# Inverted_HS_LS_switch_HI_PWR.net
KiCad netlist of a schematic drawn in Altium Designer
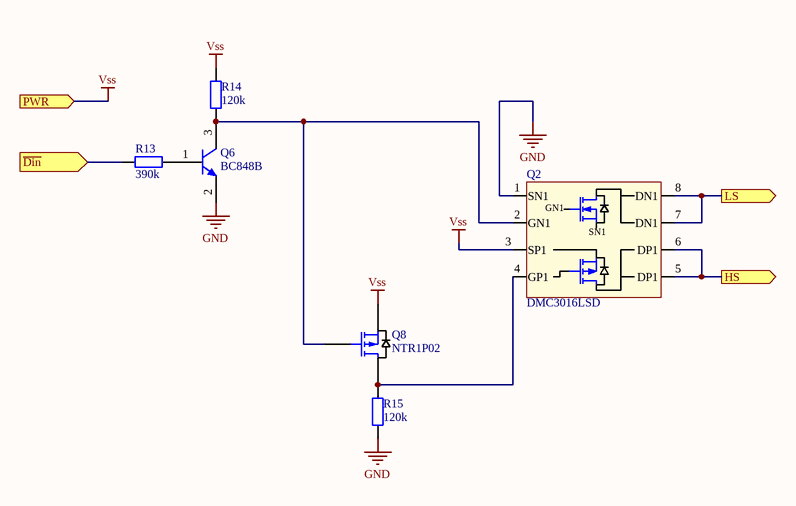
[diagram p0: Inverted_HS_LS_switch_HI_PWR.SchDoc]

(export (version "E")
  (design (tool "Eeschema 10.0.6"))
  (components
    (comp (ref "Q2")
      (value "DMC3016LSD")
      (footprint "SOIC-8_SOIC127P600X175-8N")
      (description "MOSFET N/P-CH 30V 8.2A/6.2A 8SO")
      (fields
        (field (name "MANUFACTURER") "Diodes")
        (field (name "MANUFACTURER PART NUMBER") "DMC3016LSD-13")
      )
      (libsource (lib "Datalogger") (part "DMC3016LSD"))
    )
    (comp (ref "Q6")
      (value "BC848B")
      (footprint "SOT23_N")
      (description "NPN Silicon AF Transistor, 30 V VCEO, 100 mA IC, SOT23, Reel, Green")
      (fields (field (name "MANUFACTURER") "Infineon"))
      (libsource (lib "Datalogger") (part "BC848B"))
    )
    (comp (ref "Q8")
      (value "NTR1P02")
      (footprint "SOT23_N")
      (description "NTR1P02T1G P-channel MOSFET Transistor; 1 A; 20 V; 3-Pin SOT-23")
      (fields (field (name "MANUFACTURER") "ON Semiconductor"))
      (libsource (lib "Datalogger") (part "MOSFET-P"))
    )
    (comp (ref "R13")
      (value "390k")
      (footprint "RES-1206_M")
      (description "Resistor")
      (fields (field (name "PUBLISHER") "Altium Limited"))
      (libsource (lib "") (part "Res2_1"))
    )
    (comp (ref "R14")
      (value "120k")
      (footprint "RES-1206_M")
      (description "Resistor")
      (fields (field (name "PUBLISHER") "Altium Limited"))
      (libsource (lib "") (part "Res2_2"))
    )
    (comp (ref "R15")
      (value "120k")
      (footprint "RES-1206_M")
      (description "Resistor")
      (fields (field (name "PUBLISHER") "Altium Limited"))
      (libsource (lib "Datalogger") (part "Res2"))
    )
  )
  (nets
    (net (code "1") (name "/HS") (class "Default")
      (node (ref "Q2") (pin "5") (pinfunction "DP1_5") (pintype "passive"))
      (node (ref "Q2") (pin "6") (pinfunction "DP1_6") (pintype "passive"))
    )
    (net (code "2") (name "/LS") (class "Default")
      (node (ref "Q2") (pin "7") (pinfunction "DN1_7") (pintype "passive"))
      (node (ref "Q2") (pin "8") (pinfunction "DN1_8") (pintype "passive"))
    )
    (net (code "3") (name "/~{Din}") (class "Default")
      (node (ref "R13") (pin "1") (pinfunction "1_1") (pintype "passive"))
    )
    (net (code "4") (name "GND") (class "Default")
      (node (ref "Q2") (pin "1") (pinfunction "SN1_1") (pintype "passive"))
      (node (ref "Q6") (pin "2") (pinfunction "E_2") (pintype "passive"))
      (node (ref "R15") (pin "2") (pinfunction "2_2") (pintype "passive"))
    )
    (net (code "5") (name "Net-(Q2-GN1)") (class "Default")
      (node (ref "Q2") (pin "2") (pinfunction "GN1_2") (pintype "passive"))
      (node (ref "Q6") (pin "3") (pinfunction "C_3") (pintype "passive"))
      (node (ref "Q8") (pin "1") (pinfunction "G_1") (pintype "passive"))
      (node (ref "R14") (pin "1") (pinfunction "1_1") (pintype "passive"))
    )
    (net (code "6") (name "Net-(Q2-GP1)") (class "Default")
      (node (ref "Q2") (pin "4") (pinfunction "GP1_4") (pintype "passive"))
      (node (ref "Q8") (pin "3") (pinfunction "D_3") (pintype "passive"))
      (node (ref "R15") (pin "1") (pinfunction "1_1") (pintype "passive"))
    )
    (net (code "7") (name "Net-(Q6-B)") (class "Default")
      (node (ref "Q6") (pin "1") (pinfunction "B_1") (pintype "passive"))
      (node (ref "R13") (pin "2") (pinfunction "2_2") (pintype "passive"))
    )
    (net (code "8") (name "Vss") (class "Default")
      (node (ref "Q2") (pin "3") (pinfunction "SP1_3") (pintype "passive"))
      (node (ref "Q8") (pin "2") (pinfunction "S_2") (pintype "passive"))
      (node (ref "R14") (pin "2") (pinfunction "2_2") (pintype "passive"))
    )
  )
)
